# shoes.net
KiCad netlist of a schematic drawn in EAGLE
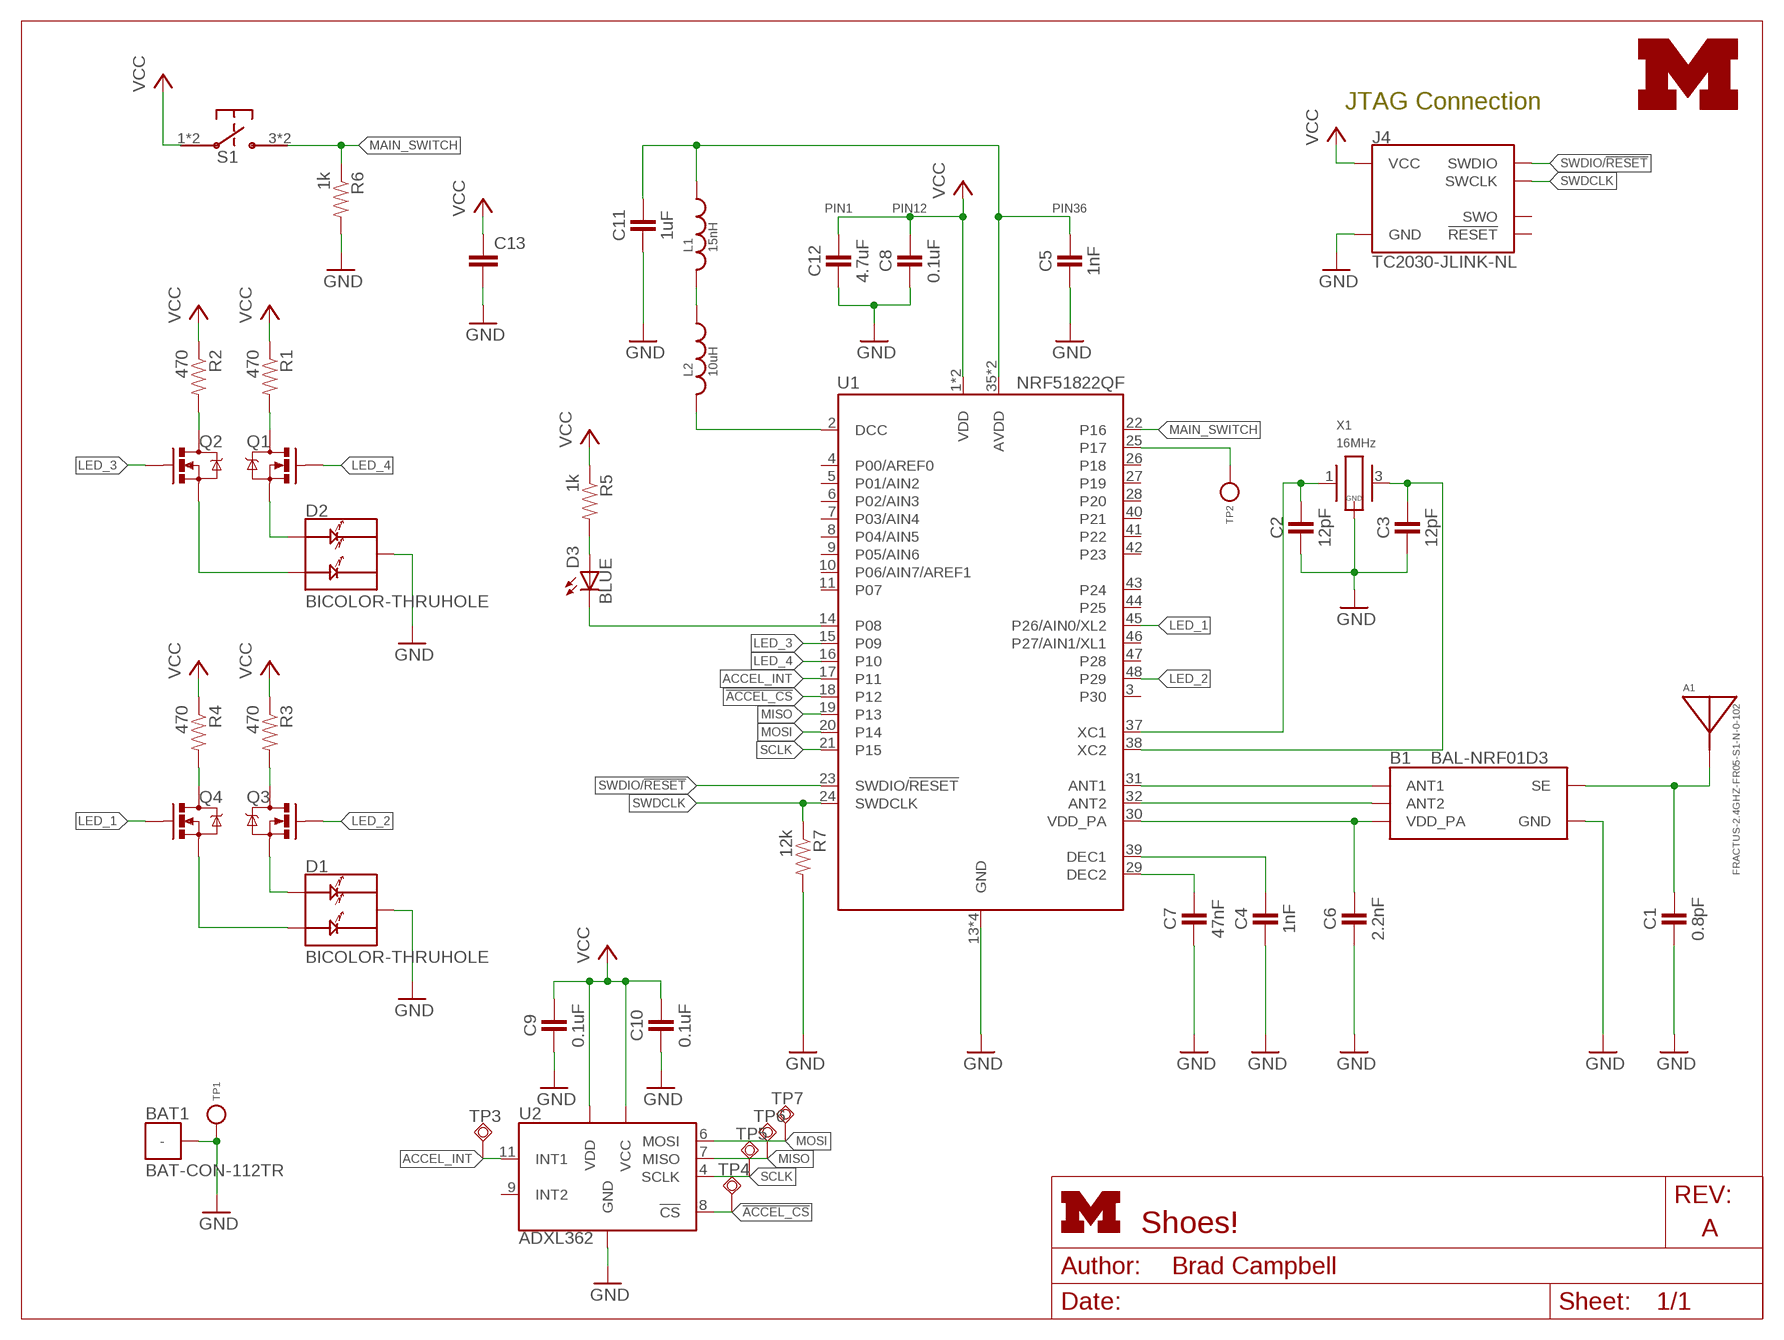
[diagram p0: schematic, sheet 1]

(export (version "E")
  (design (tool "Eeschema 10.0.6"))
  (components
    (comp (ref "A1")
      (value "FRACTUS-2.4GHZ-FR05-S1-N-0-102")
      (footprint "eagle-import:FRACTUS-ANTENNA-FR05-S1-N-0-102")
      (libsource (lib "eagle-import") (part "FRACTUS-2.4GHZ-FR05-S1-N-0-102"))
    )
    (comp (ref "B1")
      (value "BAL-NRF01D3")
      (footprint "eagle-import:BAL-NRF01D3")
      (libsource (lib "eagle-import") (part "BAL-NRF01D3"))
    )
    (comp (ref "BAT1")
      (value "BAT-CON-112TR")
      (footprint "eagle-import:BAT-CON-112TR")
      (libsource (lib "eagle-import") (part "BAT-CON-112TR"))
    )
    (comp (ref "C1")
      (value "0.8pF")
      (footprint "eagle-import:0402_CAP")
      (libsource (lib "eagle-import") (part "CAPACITOR"))
    )
    (comp (ref "C2")
      (value "12pF")
      (footprint "eagle-import:0402_CAP")
      (libsource (lib "eagle-import") (part "CAPACITOR"))
    )
    (comp (ref "C3")
      (value "12pF")
      (footprint "eagle-import:0402_CAP")
      (libsource (lib "eagle-import") (part "CAPACITOR"))
    )
    (comp (ref "C4")
      (value "1nF")
      (footprint "eagle-import:0402_CAP")
      (libsource (lib "eagle-import") (part "CAPACITOR"))
    )
    (comp (ref "C5")
      (value "1nF")
      (footprint "eagle-import:0402_CAP")
      (libsource (lib "eagle-import") (part "CAPACITOR"))
    )
    (comp (ref "C6")
      (value "2.2nF")
      (footprint "eagle-import:0402_CAP")
      (libsource (lib "eagle-import") (part "CAPACITOR"))
    )
    (comp (ref "C7")
      (value "47nF")
      (footprint "eagle-import:0402_CAP")
      (libsource (lib "eagle-import") (part "CAPACITOR"))
    )
    (comp (ref "C8")
      (value "0.1uF")
      (footprint "eagle-import:0402_CAP")
      (libsource (lib "eagle-import") (part "CAPACITOR"))
    )
    (comp (ref "C9")
      (value "0.1uF")
      (footprint "eagle-import:0402_CAP")
      (libsource (lib "eagle-import") (part "CAPACITOR"))
    )
    (comp (ref "C10")
      (value "0.1uF")
      (footprint "eagle-import:0402_CAP")
      (libsource (lib "eagle-import") (part "CAPACITOR"))
    )
    (comp (ref "C11")
      (value "1uF")
      (footprint "eagle-import:0402_CAP")
      (libsource (lib "eagle-import") (part "CAPACITOR"))
    )
    (comp (ref "C12")
      (value "4.7uF")
      (footprint "eagle-import:0402_CAP")
      (libsource (lib "eagle-import") (part "CAPACITOR"))
    )
    (comp (ref "C13")
      (value "CAP0805")
      (footprint "eagle-import:0805")
      (libsource (lib "eagle-import") (part "CAP0805"))
    )
    (comp (ref "D1")
      (value "BICOLOR-THRUHOLE")
      (footprint "eagle-import:3AXIS-0.1IN")
      (libsource (lib "eagle-import") (part "BICOLOR-THRUHOLE"))
    )
    (comp (ref "D2")
      (value "BICOLOR-THRUHOLE")
      (footprint "eagle-import:3AXIS-0.1IN")
      (libsource (lib "eagle-import") (part "BICOLOR-THRUHOLE"))
    )
    (comp (ref "D3")
      (value "BLUE")
      (footprint "eagle-import:LED-0603")
      (libsource (lib "eagle-import") (part "LED0603"))
    )
    (comp (ref "J4")
      (value "TC2030-JLINK-NL")
      (footprint "eagle-import:TC2030-IDC-NL")
      (libsource (lib "eagle-import") (part "TC2030-JLINK-NL"))
    )
    (comp (ref "L1")
      (value "15nH")
      (footprint "eagle-import:0402_CAP")
      (libsource (lib "eagle-import") (part "INDUCTOR0402"))
    )
    (comp (ref "L2")
      (value "10uH")
      (footprint "eagle-import:0603_CAP")
      (libsource (lib "eagle-import") (part "INDUCTOR0603"))
    )
    (comp (ref "LOGO3")
      (value "UMICH_SOLID_TINY")
      (footprint "eagle-import:UMICH_SOLID_50MIL")
      (libsource (lib "eagle-import") (part "UMICH_SOLID_TINY"))
    )
    (comp (ref "Q1")
      (value "MOSFET-NCHANNELXFDN-3")
      (footprint "eagle-import:XFDFN-3")
      (libsource (lib "eagle-import") (part "MOSFET-NCHANNELXFDN-3"))
    )
    (comp (ref "Q2")
      (value "MOSFET-NCHANNELXFDN-3")
      (footprint "eagle-import:XFDFN-3")
      (libsource (lib "eagle-import") (part "MOSFET-NCHANNELXFDN-3"))
    )
    (comp (ref "Q3")
      (value "MOSFET-NCHANNELXFDN-3")
      (footprint "eagle-import:XFDFN-3")
      (libsource (lib "eagle-import") (part "MOSFET-NCHANNELXFDN-3"))
    )
    (comp (ref "Q4")
      (value "MOSFET-NCHANNELXFDN-3")
      (footprint "eagle-import:XFDFN-3")
      (libsource (lib "eagle-import") (part "MOSFET-NCHANNELXFDN-3"))
    )
    (comp (ref "R1")
      (value "470")
      (footprint "eagle-import:0402_RES")
      (libsource (lib "eagle-import") (part "RESISTOR"))
    )
    (comp (ref "R2")
      (value "470")
      (footprint "eagle-import:0402_RES")
      (libsource (lib "eagle-import") (part "RESISTOR"))
    )
    (comp (ref "R3")
      (value "470")
      (footprint "eagle-import:0402_RES")
      (libsource (lib "eagle-import") (part "RESISTOR"))
    )
    (comp (ref "R4")
      (value "470")
      (footprint "eagle-import:0402_RES")
      (libsource (lib "eagle-import") (part "RESISTOR"))
    )
    (comp (ref "R5")
      (value "1k")
      (footprint "eagle-import:0402_RES")
      (libsource (lib "eagle-import") (part "RESISTOR"))
    )
    (comp (ref "R6")
      (value "1k")
      (footprint "eagle-import:0402_RES")
      (libsource (lib "eagle-import") (part "RESISTOR"))
    )
    (comp (ref "R7")
      (value "12k")
      (footprint "eagle-import:0402_RES")
      (libsource (lib "eagle-import") (part "RESISTOR"))
    )
    (comp (ref "S1")
      (value "TL3315NF100Q")
      (footprint "eagle-import:TL3315NF100Q")
      (libsource (lib "eagle-import") (part "TL3315NF100Q"))
    )
    (comp (ref "TP1")
      (value "TEST_POINT_0.020IN")
      (footprint "eagle-import:TESTPOINT_0.020IN")
      (libsource (lib "eagle-import") (part "TEST_POINT_0.020IN"))
    )
    (comp (ref "TP2")
      (value "TEST_POINT_0.020IN")
      (footprint "eagle-import:TESTPOINT_0.020IN")
      (libsource (lib "eagle-import") (part "TEST_POINT_0.020IN"))
    )
    (comp (ref "TP3")
      (value "TPSQTP06SQ")
      (footprint "eagle-import:TP06SQ")
      (libsource (lib "eagle-import") (part "TPSQTP06SQ"))
    )
    (comp (ref "TP4")
      (value "TPSQTP06SQ")
      (footprint "eagle-import:TP06SQ")
      (libsource (lib "eagle-import") (part "TPSQTP06SQ"))
    )
    (comp (ref "TP5")
      (value "TPSQTP06SQ")
      (footprint "eagle-import:TP06SQ")
      (libsource (lib "eagle-import") (part "TPSQTP06SQ"))
    )
    (comp (ref "TP6")
      (value "TPSQTP06SQ")
      (footprint "eagle-import:TP06SQ")
      (libsource (lib "eagle-import") (part "TPSQTP06SQ"))
    )
    (comp (ref "TP7")
      (value "TPSQTP06SQ")
      (footprint "eagle-import:TP06SQ")
      (libsource (lib "eagle-import") (part "TPSQTP06SQ"))
    )
    (comp (ref "U1")
      (value "NRF51822QF")
      (footprint "eagle-import:QFN-48-6MM")
      (libsource (lib "eagle-import") (part "NRF51822QF"))
    )
    (comp (ref "U2")
      (value "ADXL362")
      (footprint "eagle-import:TFLGA-16_3.3MMX3.1MM")
      (libsource (lib "eagle-import") (part "ADXL362"))
    )
    (comp (ref "X1")
      (value "16MHz")
      (footprint "eagle-import:TXC-8Y")
      (libsource (lib "eagle-import") (part "TXC-8Y"))
    )
  )
  (nets
    (net (code "1") (name "/SWDIO{slash}~{RESET}") (class "Default")
      (node (ref "J4") (pin "2") (pinfunction "SWDIO_2") (pintype "bidirectional"))
      (node (ref "U1") (pin "23") (pinfunction "SWDIO/~{RESET}_23") (pintype "bidirectional"))
    )
    (net (code "2") (name "/~{ACCEL_CS}") (class "Default")
      (node (ref "TP4") (pin "TP") (pinfunction "TP_TP") (pintype "input"))
      (node (ref "U1") (pin "18") (pinfunction "P12_18") (pintype "bidirectional"))
      (node (ref "U2") (pin "8") (pinfunction "~{CS}_8") (pintype "bidirectional"))
    )
    (net (code "3") (name "ACCEL_INT") (class "Default")
      (node (ref "TP3") (pin "TP") (pinfunction "TP_TP") (pintype "input"))
      (node (ref "U1") (pin "17") (pinfunction "P11_17") (pintype "bidirectional"))
      (node (ref "U2") (pin "11") (pinfunction "INT1_11") (pintype "bidirectional"))
    )
    (net (code "4") (name "GND") (class "Default")
      (node (ref "B1") (pin "GND") (pinfunction "GND_GND") (pintype "bidirectional"))
      (node (ref "BAT1") (pin "PAD") (pinfunction "-_PAD") (pintype "bidirectional"))
      (node (ref "C1") (pin "2") (pinfunction "2_2") (pintype "bidirectional"))
      (node (ref "C10") (pin "2") (pinfunction "2_2") (pintype "bidirectional"))
      (node (ref "C11") (pin "2") (pinfunction "2_2") (pintype "bidirectional"))
      (node (ref "C12") (pin "2") (pinfunction "2_2") (pintype "bidirectional"))
      (node (ref "C13") (pin "2") (pinfunction "2_2") (pintype "passive"))
      (node (ref "C2") (pin "2") (pinfunction "2_2") (pintype "bidirectional"))
      (node (ref "C3") (pin "2") (pinfunction "2_2") (pintype "bidirectional"))
      (node (ref "C4") (pin "2") (pinfunction "2_2") (pintype "bidirectional"))
      (node (ref "C5") (pin "2") (pinfunction "2_2") (pintype "bidirectional"))
      (node (ref "C6") (pin "2") (pinfunction "2_2") (pintype "bidirectional"))
      (node (ref "C7") (pin "2") (pinfunction "2_2") (pintype "bidirectional"))
      (node (ref "C8") (pin "2") (pinfunction "2_2") (pintype "bidirectional"))
      (node (ref "C9") (pin "2") (pinfunction "2_2") (pintype "bidirectional"))
      (node (ref "D1") (pin "M") (pinfunction "C_M") (pintype "bidirectional"))
      (node (ref "D2") (pin "M") (pinfunction "C_M") (pintype "bidirectional"))
      (node (ref "J4") (pin "5") (pinfunction "GND_5") (pintype "bidirectional"))
      (node (ref "R6") (pin "2") (pinfunction "2_2") (pintype "passive"))
      (node (ref "R7") (pin "2") (pinfunction "2_2") (pintype "passive"))
      (node (ref "TP1") (pin "TESTPOINT") (pinfunction "TESTPOINT_TESTPOINT") (pintype "bidirectional"))
      (node (ref "U1") (pin "13") (pinfunction "GND_13") (pintype "bidirectional"))
      (node (ref "U1") (pin "33") (pinfunction "GND_33") (pintype "bidirectional"))
      (node (ref "U1") (pin "34") (pinfunction "GND_34") (pintype "bidirectional"))
      (node (ref "U1") (pin "GND") (pinfunction "GND_GND") (pintype "bidirectional"))
      (node (ref "U2") (pin "12") (pinfunction "GND_12") (pintype "bidirectional"))
      (node (ref "U2") (pin "13") (pinfunction "GND_13") (pintype "bidirectional"))
      (node (ref "U2") (pin "16") (pinfunction "GND_16") (pintype "bidirectional"))
      (node (ref "X1") (pin "2") (pinfunction "GND_2") (pintype "bidirectional"))
      (node (ref "X1") (pin "4") (pinfunction "GND_4") (pintype "bidirectional"))
    )
    (net (code "5") (name "LED_1") (class "Default")
      (node (ref "Q4") (pin "G") (pinfunction "G_G") (pintype "passive"))
      (node (ref "U1") (pin "45") (pinfunction "P26/AIN0/XL2_45") (pintype "bidirectional"))
    )
    (net (code "6") (name "LED_2") (class "Default")
      (node (ref "Q3") (pin "G") (pinfunction "G_G") (pintype "passive"))
      (node (ref "U1") (pin "48") (pinfunction "P29_48") (pintype "bidirectional"))
    )
    (net (code "7") (name "LED_3") (class "Default")
      (node (ref "Q2") (pin "G") (pinfunction "G_G") (pintype "passive"))
      (node (ref "U1") (pin "15") (pinfunction "P09_15") (pintype "bidirectional"))
    )
    (net (code "8") (name "LED_4") (class "Default")
      (node (ref "Q1") (pin "G") (pinfunction "G_G") (pintype "passive"))
      (node (ref "U1") (pin "16") (pinfunction "P10_16") (pintype "bidirectional"))
    )
    (net (code "9") (name "MAIN_SWITCH") (class "Default")
      (node (ref "R6") (pin "1") (pinfunction "1_1") (pintype "passive"))
      (node (ref "S1") (pin "3") (pinfunction "P$2_3") (pintype "passive"))
      (node (ref "S1") (pin "4") (pinfunction "P$2_4") (pintype "passive"))
      (node (ref "U1") (pin "22") (pinfunction "P16_22") (pintype "bidirectional"))
    )
    (net (code "10") (name "MISO") (class "Default")
      (node (ref "TP6") (pin "TP") (pinfunction "TP_TP") (pintype "input"))
      (node (ref "U1") (pin "19") (pinfunction "P13_19") (pintype "bidirectional"))
      (node (ref "U2") (pin "7") (pinfunction "MISO_7") (pintype "bidirectional"))
    )
    (net (code "11") (name "MOSI") (class "Default")
      (node (ref "TP7") (pin "TP") (pinfunction "TP_TP") (pintype "input"))
      (node (ref "U1") (pin "20") (pinfunction "P14_20") (pintype "bidirectional"))
      (node (ref "U2") (pin "6") (pinfunction "MOSI_6") (pintype "bidirectional"))
    )
    (net (code "12") (name "Net-(A1-ANTENNA)") (class "Default")
      (node (ref "A1") (pin "1") (pinfunction "ANTENNA_1") (pintype "bidirectional"))
      (node (ref "B1") (pin "SE") (pinfunction "SE_SE") (pintype "bidirectional"))
      (node (ref "C1") (pin "1") (pinfunction "1_1") (pintype "bidirectional"))
    )
    (net (code "13") (name "Net-(B1-VDD_PA)") (class "Default")
      (node (ref "B1") (pin "VCC") (pinfunction "VDD_PA_VCC") (pintype "bidirectional"))
      (node (ref "C6") (pin "1") (pinfunction "1_1") (pintype "bidirectional"))
      (node (ref "U1") (pin "30") (pinfunction "VDD_PA_30") (pintype "bidirectional"))
    )
    (net (code "14") (name "Net-(C11-Pad1)") (class "Default")
      (node (ref "C11") (pin "1") (pinfunction "1_1") (pintype "bidirectional"))
      (node (ref "C5") (pin "1") (pinfunction "1_1") (pintype "bidirectional"))
      (node (ref "L1") (pin "1") (pinfunction "1_1") (pintype "bidirectional"))
      (node (ref "U1") (pin "35") (pinfunction "AVDD_35") (pintype "bidirectional"))
      (node (ref "U1") (pin "36") (pinfunction "AVDD_36") (pintype "bidirectional"))
    )
    (net (code "15") (name "Net-(D1-A1)") (class "Default")
      (node (ref "D1") (pin "1") (pinfunction "A1_1") (pintype "bidirectional"))
      (node (ref "Q3") (pin "S") (pinfunction "S_S") (pintype "passive"))
    )
    (net (code "16") (name "Net-(D1-A2)") (class "Default")
      (node (ref "D1") (pin "2") (pinfunction "A2_2") (pintype "bidirectional"))
      (node (ref "Q4") (pin "S") (pinfunction "S_S") (pintype "passive"))
    )
    (net (code "17") (name "Net-(D2-A1)") (class "Default")
      (node (ref "D2") (pin "1") (pinfunction "A1_1") (pintype "bidirectional"))
      (node (ref "Q1") (pin "S") (pinfunction "S_S") (pintype "passive"))
    )
    (net (code "18") (name "Net-(D2-A2)") (class "Default")
      (node (ref "D2") (pin "2") (pinfunction "A2_2") (pintype "bidirectional"))
      (node (ref "Q2") (pin "S") (pinfunction "S_S") (pintype "passive"))
    )
    (net (code "19") (name "Net-(D3-PadA)") (class "Default")
      (node (ref "D3") (pin "A") (pinfunction "A_A") (pintype "passive"))
      (node (ref "R5") (pin "2") (pinfunction "2_2") (pintype "passive"))
    )
    (net (code "20") (name "Net-(L1-Pad2)") (class "Default")
      (node (ref "L1") (pin "2") (pinfunction "2_2") (pintype "bidirectional"))
      (node (ref "L2") (pin "1") (pinfunction "1_1") (pintype "bidirectional"))
    )
    (net (code "21") (name "Net-(Q1-PadD)") (class "Default")
      (node (ref "Q1") (pin "D") (pinfunction "D_D") (pintype "passive"))
      (node (ref "R1") (pin "2") (pinfunction "2_2") (pintype "passive"))
    )
    (net (code "22") (name "Net-(Q2-PadD)") (class "Default")
      (node (ref "Q2") (pin "D") (pinfunction "D_D") (pintype "passive"))
      (node (ref "R2") (pin "2") (pinfunction "2_2") (pintype "passive"))
    )
    (net (code "23") (name "Net-(Q3-PadD)") (class "Default")
      (node (ref "Q3") (pin "D") (pinfunction "D_D") (pintype "passive"))
      (node (ref "R3") (pin "2") (pinfunction "2_2") (pintype "passive"))
    )
    (net (code "24") (name "Net-(Q4-PadD)") (class "Default")
      (node (ref "Q4") (pin "D") (pinfunction "D_D") (pintype "passive"))
      (node (ref "R4") (pin "2") (pinfunction "2_2") (pintype "passive"))
    )
    (net (code "25") (name "Net-(U1-ANT1)") (class "Default")
      (node (ref "B1") (pin "ANT1") (pinfunction "ANT1_ANT1") (pintype "bidirectional"))
      (node (ref "U1") (pin "31") (pinfunction "ANT1_31") (pintype "bidirectional"))
    )
    (net (code "26") (name "Net-(U1-ANT2)") (class "Default")
      (node (ref "B1") (pin "ANT2") (pinfunction "ANT2_ANT2") (pintype "bidirectional"))
      (node (ref "U1") (pin "32") (pinfunction "ANT2_32") (pintype "bidirectional"))
    )
    (net (code "27") (name "Net-(U1-DCC)") (class "Default")
      (node (ref "L2") (pin "2") (pinfunction "2_2") (pintype "bidirectional"))
      (node (ref "U1") (pin "2") (pinfunction "DCC_2") (pintype "bidirectional"))
    )
    (net (code "28") (name "Net-(U1-DEC1)") (class "Default")
      (node (ref "C4") (pin "1") (pinfunction "1_1") (pintype "bidirectional"))
      (node (ref "U1") (pin "39") (pinfunction "DEC1_39") (pintype "bidirectional"))
    )
    (net (code "29") (name "Net-(U1-DEC2)") (class "Default")
      (node (ref "C7") (pin "1") (pinfunction "1_1") (pintype "bidirectional"))
      (node (ref "U1") (pin "29") (pinfunction "DEC2_29") (pintype "bidirectional"))
    )
    (net (code "30") (name "Net-(U1-P08)") (class "Default")
      (node (ref "D3") (pin "C") (pinfunction "C_C") (pintype "passive"))
      (node (ref "U1") (pin "14") (pinfunction "P08_14") (pintype "bidirectional"))
    )
    (net (code "31") (name "Net-(U1-P17)") (class "Default")
      (node (ref "TP2") (pin "TESTPOINT") (pinfunction "TESTPOINT_TESTPOINT") (pintype "bidirectional"))
      (node (ref "U1") (pin "25") (pinfunction "P17_25") (pintype "bidirectional"))
    )
    (net (code "32") (name "Net-(U1-XC1)") (class "Default")
      (node (ref "C2") (pin "1") (pinfunction "1_1") (pintype "bidirectional"))
      (node (ref "U1") (pin "37") (pinfunction "XC1_37") (pintype "bidirectional"))
      (node (ref "X1") (pin "1") (pinfunction "1_1") (pintype "bidirectional"))
    )
    (net (code "33") (name "Net-(U1-XC2)") (class "Default")
      (node (ref "C3") (pin "1") (pinfunction "1_1") (pintype "bidirectional"))
      (node (ref "U1") (pin "38") (pinfunction "XC2_38") (pintype "bidirectional"))
      (node (ref "X1") (pin "3") (pinfunction "2_3") (pintype "bidirectional"))
    )
    (net (code "34") (name "SCLK") (class "Default")
      (node (ref "TP5") (pin "TP") (pinfunction "TP_TP") (pintype "input"))
      (node (ref "U1") (pin "21") (pinfunction "P15_21") (pintype "bidirectional"))
      (node (ref "U2") (pin "4") (pinfunction "SCLK_4") (pintype "bidirectional"))
    )
    (net (code "35") (name "SWDCLK") (class "Default")
      (node (ref "J4") (pin "4") (pinfunction "SWCLK_4") (pintype "bidirectional"))
      (node (ref "R7") (pin "1") (pinfunction "1_1") (pintype "passive"))
      (node (ref "U1") (pin "24") (pinfunction "SWDCLK_24") (pintype "bidirectional"))
    )
    (net (code "36") (name "VCC") (class "Default")
      (node (ref "C10") (pin "1") (pinfunction "1_1") (pintype "bidirectional"))
      (node (ref "C12") (pin "1") (pinfunction "1_1") (pintype "bidirectional"))
      (node (ref "C13") (pin "1") (pinfunction "1_1") (pintype "passive"))
      (node (ref "C8") (pin "1") (pinfunction "1_1") (pintype "bidirectional"))
      (node (ref "C9") (pin "1") (pinfunction "1_1") (pintype "bidirectional"))
      (node (ref "J4") (pin "1") (pinfunction "VCC_1") (pintype "bidirectional"))
      (node (ref "R1") (pin "1") (pinfunction "1_1") (pintype "passive"))
      (node (ref "R2") (pin "1") (pinfunction "1_1") (pintype "passive"))
      (node (ref "R3") (pin "1") (pinfunction "1_1") (pintype "passive"))
      (node (ref "R4") (pin "1") (pinfunction "1_1") (pintype "passive"))
      (node (ref "R5") (pin "1") (pinfunction "1_1") (pintype "passive"))
      (node (ref "S1") (pin "1") (pinfunction "P$1_1") (pintype "passive"))
      (node (ref "S1") (pin "2") (pinfunction "P$1_2") (pintype "passive"))
      (node (ref "U1") (pin "1") (pinfunction "VDD_1") (pintype "bidirectional"))
      (node (ref "U1") (pin "12") (pinfunction "VDD_12") (pintype "bidirectional"))
      (node (ref "U2") (pin "1") (pinfunction "VDD_1") (pintype "bidirectional"))
      (node (ref "U2") (pin "14") (pinfunction "VCC_14") (pintype "bidirectional"))
    )
    (net (code "37") (name "unconnected-(J4-SWO-Pad6)") (class "Default")
      (node (ref "J4") (pin "6") (pinfunction "SWO_6") (pintype "bidirectional"))
    )
    (net (code "38") (name "unconnected-(J4-~{RESET}-Pad3)") (class "Default")
      (node (ref "J4") (pin "3") (pinfunction "~{RESET}_3") (pintype "bidirectional"))
    )
    (net (code "39") (name "unconnected-(U1-P00{slash}AREF0-Pad4)") (class "Default")
      (node (ref "U1") (pin "4") (pinfunction "P00/AREF0_4") (pintype "bidirectional"))
    )
    (net (code "40") (name "unconnected-(U1-P01{slash}AIN2-Pad5)") (class "Default")
      (node (ref "U1") (pin "5") (pinfunction "P01/AIN2_5") (pintype "bidirectional"))
    )
    (net (code "41") (name "unconnected-(U1-P02{slash}AIN3-Pad6)") (class "Default")
      (node (ref "U1") (pin "6") (pinfunction "P02/AIN3_6") (pintype "bidirectional"))
    )
    (net (code "42") (name "unconnected-(U1-P03{slash}AIN4-Pad7)") (class "Default")
      (node (ref "U1") (pin "7") (pinfunction "P03/AIN4_7") (pintype "bidirectional"))
    )
    (net (code "43") (name "unconnected-(U1-P04{slash}AIN5-Pad8)") (class "Default")
      (node (ref "U1") (pin "8") (pinfunction "P04/AIN5_8") (pintype "bidirectional"))
    )
    (net (code "44") (name "unconnected-(U1-P05{slash}AIN6-Pad9)") (class "Default")
      (node (ref "U1") (pin "9") (pinfunction "P05/AIN6_9") (pintype "bidirectional"))
    )
    (net (code "45") (name "unconnected-(U1-P06{slash}AIN7{slash}AREF1-Pad10)") (class "Default")
      (node (ref "U1") (pin "10") (pinfunction "P06/AIN7/AREF1_10") (pintype "bidirectional"))
    )
    (net (code "46") (name "unconnected-(U1-P07-Pad11)") (class "Default")
      (node (ref "U1") (pin "11") (pinfunction "P07_11") (pintype "bidirectional"))
    )
    (net (code "47") (name "unconnected-(U1-P18-Pad26)") (class "Default")
      (node (ref "U1") (pin "26") (pinfunction "P18_26") (pintype "bidirectional"))
    )
    (net (code "48") (name "unconnected-(U1-P19-Pad27)") (class "Default")
      (node (ref "U1") (pin "27") (pinfunction "P19_27") (pintype "bidirectional"))
    )
    (net (code "49") (name "unconnected-(U1-P20-Pad28)") (class "Default")
      (node (ref "U1") (pin "28") (pinfunction "P20_28") (pintype "bidirectional"))
    )
    (net (code "50") (name "unconnected-(U1-P21-Pad40)") (class "Default")
      (node (ref "U1") (pin "40") (pinfunction "P21_40") (pintype "bidirectional"))
    )
    (net (code "51") (name "unconnected-(U1-P22-Pad41)") (class "Default")
      (node (ref "U1") (pin "41") (pinfunction "P22_41") (pintype "bidirectional"))
    )
    (net (code "52") (name "unconnected-(U1-P23-Pad42)") (class "Default")
      (node (ref "U1") (pin "42") (pinfunction "P23_42") (pintype "bidirectional"))
    )
    (net (code "53") (name "unconnected-(U1-P24-Pad43)") (class "Default")
      (node (ref "U1") (pin "43") (pinfunction "P24_43") (pintype "bidirectional"))
    )
    (net (code "54") (name "unconnected-(U1-P25-Pad44)") (class "Default")
      (node (ref "U1") (pin "44") (pinfunction "P25_44") (pintype "bidirectional"))
    )
    (net (code "55") (name "unconnected-(U1-P27{slash}AIN1{slash}XL1-Pad46)") (class "Default")
      (node (ref "U1") (pin "46") (pinfunction "P27/AIN1/XL1_46") (pintype "bidirectional"))
    )
    (net (code "56") (name "unconnected-(U1-P28-Pad47)") (class "Default")
      (node (ref "U1") (pin "47") (pinfunction "P28_47") (pintype "bidirectional"))
    )
    (net (code "57") (name "unconnected-(U1-P30-Pad3)") (class "Default")
      (node (ref "U1") (pin "3") (pinfunction "P30_3") (pintype "bidirectional"))
    )
    (net (code "58") (name "unconnected-(U2-INT2-Pad9)") (class "Default")
      (node (ref "U2") (pin "9") (pinfunction "INT2_9") (pintype "bidirectional"))
    )
  )
)
